# Sheet1.net
KiCad netlist of a schematic drawn in Altium Designer
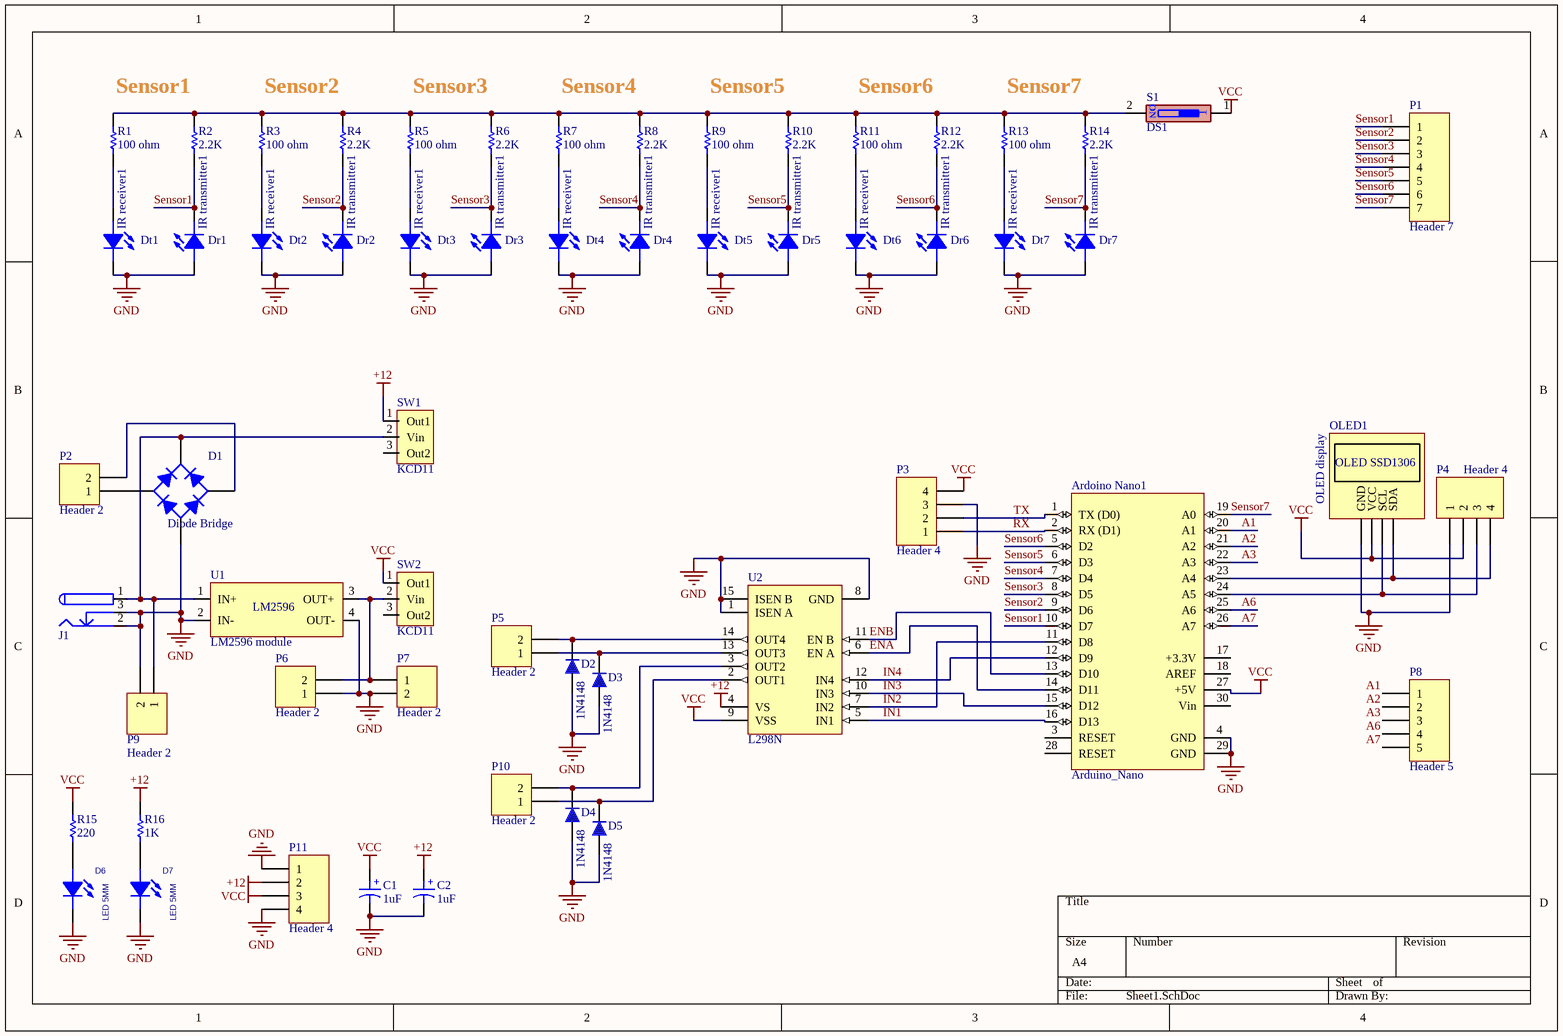
[diagram p0: Sheet1.SchDoc]

(export (version "E")
  (design (tool "Eeschema 10.0.6"))
  (components
    (comp (ref "Ardoino Nano1")
      (value "Arduino_Nano")
      (footprint "Arduino_Nano")
      (libsource (lib "MyLibrary") (part "Arduino_Nano"))
    )
    (comp (ref "C1")
      (value "1uF")
      (footprint "Cap electrolitic radial 10x16-5")
      (description "Cap electrolitic radial")
      (fields (field (name "DESIGNER") "Abbas Basereh"))
      (libsource (lib "Altium") (part "Cap ELECTROLITIC TOTAL SIZE"))
    )
    (comp (ref "C2")
      (value "1uF")
      (footprint "Cap electrolitic radial 10x16-5")
      (description "Cap electrolitic radial")
      (fields (field (name "DESIGNER") "Abbas Basereh"))
      (libsource (lib "Altium") (part "Cap ELECTROLITIC TOTAL SIZE"))
    )
    (comp (ref "D1")
      (value "Diode Bridge")
      (footprint "Bridge KBP PACKAGE")
      (description "Full Wave Diode Bridge")
      (fields (field (name "DESIGNER") "Abbas Basereh"))
      (libsource (lib "Altium") (part "Diode Bridge TOTAL SIZE"))
    )
    (comp (ref "D2")
      (value "1N4148")
      (footprint "DO 35")
      (description "DIODE GEN PURP 100V 200MA DO35")
      (fields (field (name "PUBLISHER") "Abbas Basereh"))
      (libsource (lib "Altium") (part "1N4148"))
    )
    (comp (ref "D3")
      (value "1N4148")
      (footprint "DO 35")
      (description "DIODE GEN PURP 100V 200MA DO35")
      (fields (field (name "PUBLISHER") "Abbas Basereh"))
      (libsource (lib "Altium") (part "1N4148"))
    )
    (comp (ref "D4")
      (value "1N4148")
      (footprint "DO 35")
      (description "DIODE GEN PURP 100V 200MA DO35")
      (fields (field (name "PUBLISHER") "Abbas Basereh"))
      (libsource (lib "Altium") (part "1N4148"))
    )
    (comp (ref "D5")
      (value "1N4148")
      (footprint "DO 35")
      (description "DIODE GEN PURP 100V 200MA DO35")
      (fields (field (name "PUBLISHER") "Abbas Basereh"))
      (libsource (lib "Altium") (part "1N4148"))
    )
    (comp (ref "D6")
      (value "LED 5MM")
      (footprint "LED5MM_RED")
      (description "Light Emitting Diode")
      (fields (field (name "DESIGNER") "Abbas Basereh"))
      (libsource (lib "Altium") (part "LED 5MM"))
    )
    (comp (ref "D7")
      (value "LED 5MM")
      (footprint "LED5MM_RED")
      (description "Light Emitting Diode")
      (fields (field (name "DESIGNER") "Abbas Basereh"))
      (libsource (lib "Altium") (part "LED 5MM"))
    )
    (comp (ref "Dr1")
      (value "IR transmitter1")
      (footprint "LED3mm_GRN")
      (description "Light Emitting Diode")
      (fields (field (name "DESIGNER") "Ali Hafizi"))
      (libsource (lib "Altium") (part "LED 3MM"))
    )
    (comp (ref "Dr2")
      (value "IR transmitter1")
      (footprint "LED3mm_GRN")
      (description "Light Emitting Diode")
      (fields (field (name "DESIGNER") "Ali Hafizi"))
      (libsource (lib "Altium") (part "LED 3MM"))
    )
    (comp (ref "Dr3")
      (value "IR transmitter1")
      (footprint "LED3mm_GRN")
      (description "Light Emitting Diode")
      (fields (field (name "DESIGNER") "Ali Hafizi"))
      (libsource (lib "Altium") (part "LED 3MM"))
    )
    (comp (ref "Dr4")
      (value "IR transmitter1")
      (footprint "LED3mm_GRN")
      (description "Light Emitting Diode")
      (fields (field (name "DESIGNER") "Ali Hafizi"))
      (libsource (lib "Altium") (part "LED 3MM"))
    )
    (comp (ref "Dr5")
      (value "IR transmitter1")
      (footprint "LED3mm_GRN")
      (description "Light Emitting Diode")
      (fields (field (name "DESIGNER") "Ali Hafizi"))
      (libsource (lib "Altium") (part "LED 3MM"))
    )
    (comp (ref "Dr6")
      (value "IR transmitter1")
      (footprint "LED3mm_GRN")
      (description "Light Emitting Diode")
      (fields (field (name "DESIGNER") "Ali Hafizi"))
      (libsource (lib "Altium") (part "LED 3MM"))
    )
    (comp (ref "Dr7")
      (value "IR transmitter1")
      (footprint "LED3mm_GRN")
      (description "Light Emitting Diode")
      (fields (field (name "DESIGNER") "Ali Hafizi"))
      (libsource (lib "Altium") (part "LED 3MM"))
    )
    (comp (ref "Dt1")
      (value "IR receiver1")
      (footprint "LED3mm_GRN")
      (description "Light Emitting Diode")
      (fields (field (name "DESIGNER") "Ali Hafizi"))
      (libsource (lib "Altium") (part "LED 3MM"))
    )
    (comp (ref "Dt2")
      (value "IR receiver1")
      (footprint "LED3mm_GRN")
      (description "Light Emitting Diode")
      (fields (field (name "DESIGNER") "Ali Hafizi"))
      (libsource (lib "Altium") (part "LED 3MM"))
    )
    (comp (ref "Dt3")
      (value "IR receiver1")
      (footprint "LED3mm_GRN")
      (description "Light Emitting Diode")
      (fields (field (name "DESIGNER") "Ali Hafizi"))
      (libsource (lib "Altium") (part "LED 3MM"))
    )
    (comp (ref "Dt4")
      (value "IR receiver1")
      (footprint "LED3mm_GRN")
      (description "Light Emitting Diode")
      (fields (field (name "DESIGNER") "Ali Hafizi"))
      (libsource (lib "Altium") (part "LED 3MM"))
    )
    (comp (ref "Dt5")
      (value "IR receiver1")
      (footprint "LED3mm_GRN")
      (description "Light Emitting Diode")
      (fields (field (name "DESIGNER") "Ali Hafizi"))
      (libsource (lib "Altium") (part "LED 3MM"))
    )
    (comp (ref "Dt6")
      (value "IR receiver1")
      (footprint "LED3mm_GRN")
      (description "Light Emitting Diode")
      (fields (field (name "DESIGNER") "Ali Hafizi"))
      (libsource (lib "Altium") (part "LED 3MM"))
    )
    (comp (ref "Dt7")
      (value "IR receiver1")
      (footprint "LED3mm_GRN")
      (description "Light Emitting Diode")
      (fields (field (name "DESIGNER") "Ali Hafizi"))
      (libsource (lib "Altium") (part "LED 3MM"))
    )
    (comp (ref "J1")
      (value "DC Power Jack")
      (footprint "DC Power Jack 1")
      (description "DC Power Jack. Center Pin 2.5mm. Diameter: 5.7mm")
      (fields (field (name "DESIGNER") "Ali Hafizi"))
      (libsource (lib "Altium") (part "DC Power Jack"))
    )
    (comp (ref "OLED1")
      (value "OLED display")
      (footprint "OLED-SSD1306")
      (description "OLED display SSD1306 0.96 inch 64*128px")
      (libsource (lib "MyLibrary") (part "OLED-SSD1306"))
    )
    (comp (ref "P1")
      (value "Header 7")
      (footprint "HDR1X7")
      (description "Header, 7-Pin")
      (fields (field (name "PUBLISHER") "Altium Limited"))
      (libsource (lib "Altium") (part "Header 7"))
    )
    (comp (ref "P2")
      (value "Header 2")
      (footprint "HDR1X2")
      (description "Header, 2-Pin")
      (fields (field (name "PUBLISHER") "Altium Limited"))
      (libsource (lib "Altium") (part "Header 2"))
    )
    (comp (ref "P3")
      (value "Header 4")
      (footprint "HDR1X4")
      (description "Header, 4-Pin")
      (fields (field (name "PUBLISHER") "Altium Limited"))
      (libsource (lib "") (part "Header 4_2"))
    )
    (comp (ref "P4")
      (value "Header 4")
      (footprint "HDR1X4")
      (description "Header, 4-Pin")
      (fields (field (name "PUBLISHER") "Altium Limited"))
      (libsource (lib "Altium") (part "Header 4"))
    )
    (comp (ref "P5")
      (value "Header 2")
      (footprint "HDR1X2")
      (description "Header, 2-Pin")
      (fields (field (name "PUBLISHER") "Altium Limited"))
      (libsource (lib "Altium") (part "Header 2"))
    )
    (comp (ref "P6")
      (value "Header 2")
      (footprint "HDR1X2")
      (description "Header, 2-Pin")
      (fields (field (name "PUBLISHER") "Altium Limited"))
      (libsource (lib "Altium") (part "Header 2"))
    )
    (comp (ref "P7")
      (value "Header 2")
      (footprint "HDR1X2")
      (description "Header, 2-Pin")
      (fields (field (name "PUBLISHER") "Altium Limited"))
      (libsource (lib "") (part "Header 2_1"))
    )
    (comp (ref "P8")
      (value "Header 5")
      (footprint "HDR1X5")
      (description "Header, 5-Pin")
      (fields (field (name "PUBLISHER") "Altium Limited"))
      (libsource (lib "Altium") (part "Header 5"))
    )
    (comp (ref "P9")
      (value "Header 2")
      (footprint "HDR1X2")
      (description "Header, 2-Pin")
      (fields (field (name "PUBLISHER") "Altium Limited"))
      (libsource (lib "") (part "Header 2_2"))
    )
    (comp (ref "P10")
      (value "Header 2")
      (footprint "HDR1X2")
      (description "Header, 2-Pin")
      (fields (field (name "PUBLISHER") "Altium Limited"))
      (libsource (lib "Altium") (part "Header 2"))
    )
    (comp (ref "P11")
      (value "Header 4")
      (footprint "HDR1X4")
      (description "Header, 4-Pin")
      (fields (field (name "PUBLISHER") "Altium Limited"))
      (libsource (lib "") (part "Header 4_1"))
    )
    (comp (ref "R1")
      (value "100 ohm")
      (footprint "Axial 0_25 W, 0_4 IN LEAD PITCH")
      (description "RES Axial 0.25W")
      (fields (field (name "DESIGNER") "Abbas Basereh"))
      (libsource (lib "Altium") (part "RES Axial 0.25W"))
    )
    (comp (ref "R2")
      (value "2.2K")
      (footprint "Axial 0_25 W, 0_4 IN LEAD PITCH")
      (description "RES Axial 0.25W")
      (fields (field (name "DESIGNER") "Abbas Basereh"))
      (libsource (lib "Altium") (part "RES Axial 0.25W"))
    )
    (comp (ref "R3")
      (value "100 ohm")
      (footprint "Axial 0_25 W, 0_4 IN LEAD PITCH")
      (description "RES Axial 0.25W")
      (fields (field (name "DESIGNER") "Abbas Basereh"))
      (libsource (lib "Altium") (part "RES Axial 0.25W"))
    )
    (comp (ref "R4")
      (value "2.2K")
      (footprint "Axial 0_25 W, 0_4 IN LEAD PITCH")
      (description "RES Axial 0.25W")
      (fields (field (name "DESIGNER") "Abbas Basereh"))
      (libsource (lib "Altium") (part "RES Axial 0.25W"))
    )
    (comp (ref "R5")
      (value "100 ohm")
      (footprint "Axial 0_25 W, 0_4 IN LEAD PITCH")
      (description "RES Axial 0.25W")
      (fields (field (name "DESIGNER") "Abbas Basereh"))
      (libsource (lib "Altium") (part "RES Axial 0.25W"))
    )
    (comp (ref "R6")
      (value "2.2K")
      (footprint "Axial 0_25 W, 0_4 IN LEAD PITCH")
      (description "RES Axial 0.25W")
      (fields (field (name "DESIGNER") "Abbas Basereh"))
      (libsource (lib "Altium") (part "RES Axial 0.25W"))
    )
    (comp (ref "R7")
      (value "100 ohm")
      (footprint "Axial 0_25 W, 0_4 IN LEAD PITCH")
      (description "RES Axial 0.25W")
      (fields (field (name "DESIGNER") "Abbas Basereh"))
      (libsource (lib "Altium") (part "RES Axial 0.25W"))
    )
    (comp (ref "R8")
      (value "2.2K")
      (footprint "Axial 0_25 W, 0_4 IN LEAD PITCH")
      (description "RES Axial 0.25W")
      (fields (field (name "DESIGNER") "Abbas Basereh"))
      (libsource (lib "Altium") (part "RES Axial 0.25W"))
    )
    (comp (ref "R9")
      (value "100 ohm")
      (footprint "Axial 0_25 W, 0_4 IN LEAD PITCH")
      (description "RES Axial 0.25W")
      (fields (field (name "DESIGNER") "Abbas Basereh"))
      (libsource (lib "Altium") (part "RES Axial 0.25W"))
    )
    (comp (ref "R10")
      (value "2.2K")
      (footprint "Axial 0_25 W, 0_4 IN LEAD PITCH")
      (description "RES Axial 0.25W")
      (fields (field (name "DESIGNER") "Abbas Basereh"))
      (libsource (lib "Altium") (part "RES Axial 0.25W"))
    )
    (comp (ref "R11")
      (value "100 ohm")
      (footprint "Axial 0_25 W, 0_4 IN LEAD PITCH")
      (description "RES Axial 0.25W")
      (fields (field (name "DESIGNER") "Abbas Basereh"))
      (libsource (lib "Altium") (part "RES Axial 0.25W"))
    )
    (comp (ref "R12")
      (value "2.2K")
      (footprint "Axial 0_25 W, 0_4 IN LEAD PITCH")
      (description "RES Axial 0.25W")
      (fields (field (name "DESIGNER") "Abbas Basereh"))
      (libsource (lib "Altium") (part "RES Axial 0.25W"))
    )
    (comp (ref "R13")
      (value "100 ohm")
      (footprint "Axial 0_25 W, 0_4 IN LEAD PITCH")
      (description "RES Axial 0.25W")
      (fields (field (name "DESIGNER") "Abbas Basereh"))
      (libsource (lib "Altium") (part "RES Axial 0.25W"))
    )
    (comp (ref "R14")
      (value "2.2K")
      (footprint "Axial 0_25 W, 0_4 IN LEAD PITCH")
      (description "RES Axial 0.25W")
      (fields (field (name "DESIGNER") "Abbas Basereh"))
      (libsource (lib "Altium") (part "RES Axial 0.25W"))
    )
    (comp (ref "R15")
      (value "220")
      (footprint "Axial 0_25 W, 0_4 IN LEAD PITCH")
      (description "RES Axial 0.25W")
      (fields (field (name "DESIGNER") "Abbas Basereh"))
      (libsource (lib "Altium") (part "RES Axial 0.25W"))
    )
    (comp (ref "R16")
      (value "1K")
      (footprint "Axial 0_25 W, 0_4 IN LEAD PITCH")
      (description "RES Axial 0.25W")
      (fields (field (name "DESIGNER") "Abbas Basereh"))
      (libsource (lib "Altium") (part "RES Axial 0.25W"))
    )
    (comp (ref "S1")
      (value "DS1")
      (footprint "DIP Switch x1")
      (description "1 BIT DIP Switch")
      (libsource (lib "Altium") (part "DIP Switch 1"))
    )
    (comp (ref "SW1")
      (value "KCD11")
      (footprint "KCD11 rocker switch")
      (description "KCD11 rocker switch 2 state off/on")
      (libsource (lib "MyLibrary") (part "KCD11"))
    )
    (comp (ref "SW2")
      (value "KCD11")
      (footprint "KCD11 rocker switch")
      (description "KCD11 rocker switch 2 state off/on")
      (libsource (lib "MyLibrary") (part "KCD11"))
    )
    (comp (ref "U1")
      (value "LM2596 module")
      (footprint "LM2596 module")
      (description "LM2596 DC-DC module 1.25V-30V 3A")
      (libsource (lib "MyLibrary") (part "LM2596 module"))
    )
    (comp (ref "U2")
      (value "L298N")
      (footprint "Multiwatt15V")
      (description "Dual Full Bridge Driver")
      (fields (field (name "PUBLISHER") "Altium Limited"))
      (libsource (lib "Altium") (part "L298N"))
    )
  )
  (nets
    (net (code "1") (name "+12") (class "Default")
      (node (ref "C2") (pin "1") (pinfunction "1_1") (pintype "passive"))
      (node (ref "P11") (pin "2") (pinfunction "2_2") (pintype "passive"))
      (node (ref "R16") (pin "2") (pinfunction "2_2") (pintype "passive"))
      (node (ref "SW1") (pin "1") (pinfunction "Out1_1") (pintype "passive"))
      (node (ref "U2") (pin "4") (pinfunction "VS_4") (pintype "power_in"))
    )
    (net (code "2") (name "/A1") (class "Default")
      (node (ref "Ardoino Nano1") (pin "20") (pinfunction "A1_20") (pintype "bidirectional"))
      (node (ref "P8") (pin "1") (pinfunction "1_1") (pintype "passive"))
    )
    (net (code "3") (name "/A2") (class "Default")
      (node (ref "Ardoino Nano1") (pin "21") (pinfunction "A2_21") (pintype "bidirectional"))
      (node (ref "P8") (pin "2") (pinfunction "2_2") (pintype "passive"))
    )
    (net (code "4") (name "/A3") (class "Default")
      (node (ref "Ardoino Nano1") (pin "22") (pinfunction "A3_22") (pintype "bidirectional"))
      (node (ref "P8") (pin "3") (pinfunction "3_3") (pintype "passive"))
    )
    (net (code "5") (name "/A6") (class "Default")
      (node (ref "Ardoino Nano1") (pin "25") (pinfunction "A6_25") (pintype "bidirectional"))
      (node (ref "P8") (pin "4") (pinfunction "4_4") (pintype "passive"))
    )
    (net (code "6") (name "/A7") (class "Default")
      (node (ref "Ardoino Nano1") (pin "26") (pinfunction "A7_26") (pintype "bidirectional"))
      (node (ref "P8") (pin "5") (pinfunction "5_5") (pintype "passive"))
    )
    (net (code "7") (name "/ENA") (class "Default")
      (node (ref "Ardoino Nano1") (pin "14") (pinfunction "D11_14") (pintype "bidirectional"))
      (node (ref "U2") (pin "6") (pinfunction "EN_A_6") (pintype "input"))
    )
    (net (code "8") (name "/ENB") (class "Default")
      (node (ref "Ardoino Nano1") (pin "13") (pinfunction "D10_13") (pintype "bidirectional"))
      (node (ref "U2") (pin "11") (pinfunction "EN_B_11") (pintype "input"))
    )
    (net (code "9") (name "/IN1") (class "Default")
      (node (ref "Ardoino Nano1") (pin "16") (pinfunction "D13_16") (pintype "bidirectional"))
      (node (ref "U2") (pin "5") (pinfunction "IN1_5") (pintype "input"))
    )
    (net (code "10") (name "/IN2") (class "Default")
      (node (ref "Ardoino Nano1") (pin "11") (pinfunction "D8_11") (pintype "bidirectional"))
      (node (ref "U2") (pin "7") (pinfunction "IN2_7") (pintype "input"))
    )
    (net (code "11") (name "/IN3") (class "Default")
      (node (ref "Ardoino Nano1") (pin "15") (pinfunction "D12_15") (pintype "bidirectional"))
      (node (ref "U2") (pin "10") (pinfunction "IN3_10") (pintype "input"))
    )
    (net (code "12") (name "/IN4") (class "Default")
      (node (ref "Ardoino Nano1") (pin "12") (pinfunction "D9_12") (pintype "bidirectional"))
      (node (ref "U2") (pin "12") (pinfunction "IN4_12") (pintype "input"))
    )
    (net (code "13") (name "/RX") (class "Default")
      (node (ref "Ardoino Nano1") (pin "2") (pinfunction "RX_(D1)_2") (pintype "bidirectional"))
      (node (ref "P3") (pin "1") (pinfunction "1_1") (pintype "passive"))
    )
    (net (code "14") (name "/Sensor1") (class "Default")
      (node (ref "Ardoino Nano1") (pin "10") (pinfunction "D7_10") (pintype "bidirectional"))
      (node (ref "Dr1") (pin "2") (pinfunction "CATHODE_2") (pintype "passive"))
      (node (ref "P1") (pin "1") (pinfunction "1_1") (pintype "passive"))
      (node (ref "R2") (pin "1") (pinfunction "1_1") (pintype "passive"))
    )
    (net (code "15") (name "/Sensor2") (class "Default")
      (node (ref "Ardoino Nano1") (pin "9") (pinfunction "D6_9") (pintype "bidirectional"))
      (node (ref "Dr2") (pin "2") (pinfunction "CATHODE_2") (pintype "passive"))
      (node (ref "P1") (pin "2") (pinfunction "2_2") (pintype "passive"))
      (node (ref "R4") (pin "1") (pinfunction "1_1") (pintype "passive"))
    )
    (net (code "16") (name "/Sensor3") (class "Default")
      (node (ref "Ardoino Nano1") (pin "8") (pinfunction "D5_8") (pintype "bidirectional"))
      (node (ref "Dr3") (pin "2") (pinfunction "CATHODE_2") (pintype "passive"))
      (node (ref "P1") (pin "3") (pinfunction "3_3") (pintype "passive"))
      (node (ref "R6") (pin "1") (pinfunction "1_1") (pintype "passive"))
    )
    (net (code "17") (name "/Sensor4") (class "Default")
      (node (ref "Ardoino Nano1") (pin "7") (pinfunction "D4_7") (pintype "bidirectional"))
      (node (ref "Dr4") (pin "2") (pinfunction "CATHODE_2") (pintype "passive"))
      (node (ref "P1") (pin "4") (pinfunction "4_4") (pintype "passive"))
      (node (ref "R8") (pin "1") (pinfunction "1_1") (pintype "passive"))
    )
    (net (code "18") (name "/Sensor5") (class "Default")
      (node (ref "Ardoino Nano1") (pin "6") (pinfunction "D3_6") (pintype "bidirectional"))
      (node (ref "Dr5") (pin "2") (pinfunction "CATHODE_2") (pintype "passive"))
      (node (ref "P1") (pin "5") (pinfunction "5_5") (pintype "passive"))
      (node (ref "R10") (pin "1") (pinfunction "1_1") (pintype "passive"))
    )
    (net (code "19") (name "/Sensor6") (class "Default")
      (node (ref "Ardoino Nano1") (pin "5") (pinfunction "D2_5") (pintype "bidirectional"))
      (node (ref "Dr6") (pin "2") (pinfunction "CATHODE_2") (pintype "passive"))
      (node (ref "P1") (pin "6") (pinfunction "6_6") (pintype "passive"))
      (node (ref "R12") (pin "1") (pinfunction "1_1") (pintype "passive"))
    )
    (net (code "20") (name "/Sensor7") (class "Default")
      (node (ref "Ardoino Nano1") (pin "19") (pinfunction "A0_19") (pintype "bidirectional"))
      (node (ref "Dr7") (pin "2") (pinfunction "CATHODE_2") (pintype "passive"))
      (node (ref "P1") (pin "7") (pinfunction "7_7") (pintype "passive"))
      (node (ref "R14") (pin "1") (pinfunction "1_1") (pintype "passive"))
    )
    (net (code "21") (name "/TX") (class "Default")
      (node (ref "Ardoino Nano1") (pin "1") (pinfunction "TX_(D0)_1") (pintype "bidirectional"))
      (node (ref "P3") (pin "2") (pinfunction "2_2") (pintype "passive"))
    )
    (net (code "22") (name "GND") (class "Default")
      (node (ref "Ardoino Nano1") (pin "29") (pinfunction "GND_29") (pintype "passive"))
      (node (ref "Ardoino Nano1") (pin "4") (pinfunction "GND_4") (pintype "passive"))
      (node (ref "C1") (pin "2") (pinfunction "2_2") (pintype "passive"))
      (node (ref "C2") (pin "2") (pinfunction "2_2") (pintype "passive"))
      (node (ref "D1") (pin "4") (pinfunction "-_4") (pintype "passive"))
      (node (ref "D2") (pin "1") (pintype "passive"))
      (node (ref "D3") (pin "1") (pintype "passive"))
      (node (ref "D4") (pin "1") (pintype "passive"))
      (node (ref "D5") (pin "1") (pintype "passive"))
      (node (ref "D6") (pin "2") (pinfunction "CATHODE_2") (pintype "passive"))
      (node (ref "D7") (pin "2") (pinfunction "CATHODE_2") (pintype "passive"))
      (node (ref "Dr1") (pin "1") (pinfunction "ANODE_1") (pintype "passive"))
      (node (ref "Dr2") (pin "1") (pinfunction "ANODE_1") (pintype "passive"))
      (node (ref "Dr3") (pin "1") (pinfunction "ANODE_1") (pintype "passive"))
      (node (ref "Dr4") (pin "1") (pinfunction "ANODE_1") (pintype "passive"))
      (node (ref "Dr5") (pin "1") (pinfunction "ANODE_1") (pintype "passive"))
      (node (ref "Dr6") (pin "1") (pinfunction "ANODE_1") (pintype "passive"))
      (node (ref "Dr7") (pin "1") (pinfunction "ANODE_1") (pintype "passive"))
      (node (ref "Dt1") (pin "2") (pinfunction "CATHODE_2") (pintype "passive"))
      (node (ref "Dt2") (pin "2") (pinfunction "CATHODE_2") (pintype "passive"))
      (node (ref "Dt3") (pin "2") (pinfunction "CATHODE_2") (pintype "passive"))
      (node (ref "Dt4") (pin "2") (pinfunction "CATHODE_2") (pintype "passive"))
      (node (ref "Dt5") (pin "2") (pinfunction "CATHODE_2") (pintype "passive"))
      (node (ref "Dt6") (pin "2") (pinfunction "CATHODE_2") (pintype "passive"))
      (node (ref "Dt7") (pin "2") (pinfunction "CATHODE_2") (pintype "passive"))
      (node (ref "J1") (pin "2") (pinfunction "2_2") (pintype "power_in"))
      (node (ref "J1") (pin "3") (pinfunction "3_3") (pintype "power_in"))
      (node (ref "OLED1") (pin "GND") (pinfunction "GND_GND") (pintype "passive"))
      (node (ref "P11") (pin "1") (pinfunction "1_1") (pintype "passive"))
      (node (ref "P11") (pin "4") (pinfunction "4_4") (pintype "passive"))
      (node (ref "P3") (pin "3") (pinfunction "3_3") (pintype "passive"))
      (node (ref "P4") (pin "1") (pinfunction "1_1") (pintype "passive"))
      (node (ref "P6") (pin "1") (pinfunction "1_1") (pintype "passive"))
      (node (ref "P7") (pin "2") (pinfunction "2_2") (pintype "passive"))
      (node (ref "P9") (pin "2") (pinfunction "2_2") (pintype "passive"))
      (node (ref "U1") (pin "2") (pinfunction "IN-_2") (pintype "passive"))
      (node (ref "U1") (pin "4") (pinfunction "OUT-_4") (pintype "passive"))
      (node (ref "U2") (pin "1") (pinfunction "ISEN_A_1") (pintype "passive"))
      (node (ref "U2") (pin "15") (pinfunction "ISEN_B_15") (pintype "passive"))
      (node (ref "U2") (pin "8") (pinfunction "GND_8") (pintype "power_in"))
    )
    (net (code "23") (name "Net-(Ardoino Nano1-A4)") (class "Default")
      (node (ref "Ardoino Nano1") (pin "23") (pinfunction "A4_23") (pintype "bidirectional"))
      (node (ref "OLED1") (pin "SDA") (pinfunction "SDA_SDA") (pintype "passive"))
      (node (ref "P4") (pin "4") (pinfunction "4_4") (pintype "passive"))
    )
    (net (code "24") (name "Net-(Ardoino Nano1-A5)") (class "Default")
      (node (ref "Ardoino Nano1") (pin "24") (pinfunction "A5_24") (pintype "bidirectional"))
      (node (ref "OLED1") (pin "SCL") (pinfunction "SCL_SCL") (pintype "passive"))
      (node (ref "P4") (pin "3") (pinfunction "3_3") (pintype "passive"))
    )
    (net (code "25") (name "Net-(D1-+)") (class "Default")
      (node (ref "D1") (pin "1") (pinfunction "+_1") (pintype "passive"))
      (node (ref "J1") (pin "1") (pinfunction "1_1") (pintype "power_in"))
      (node (ref "P9") (pin "1") (pinfunction "1_1") (pintype "passive"))
      (node (ref "SW1") (pin "2") (pinfunction "Vin_2") (pintype "passive"))
      (node (ref "U1") (pin "1") (pinfunction "IN+_1") (pintype "passive"))
    )
    (net (code "26") (name "Net-(D1-AC-Pad2)") (class "Default")
      (node (ref "D1") (pin "2") (pinfunction "AC_2") (pintype "passive"))
      (node (ref "P2") (pin "1") (pinfunction "1_1") (pintype "passive"))
    )
    (net (code "27") (name "Net-(D1-AC-Pad3)") (class "Default")
      (node (ref "D1") (pin "3") (pinfunction "AC_3") (pintype "passive"))
      (node (ref "P2") (pin "2") (pinfunction "2_2") (pintype "passive"))
    )
    (net (code "28") (name "Net-(D6-ANODE)") (class "Default")
      (node (ref "D6") (pin "1") (pinfunction "ANODE_1") (pintype "passive"))
      (node (ref "R15") (pin "1") (pinfunction "1_1") (pintype "passive"))
    )
    (net (code "29") (name "Net-(D7-ANODE)") (class "Default")
      (node (ref "D7") (pin "1") (pinfunction "ANODE_1") (pintype "passive"))
      (node (ref "R16") (pin "1") (pinfunction "1_1") (pintype "passive"))
    )
    (net (code "30") (name "Net-(Dt1-ANODE)") (class "Default")
      (node (ref "Dt1") (pin "1") (pinfunction "ANODE_1") (pintype "passive"))
      (node (ref "R1") (pin "1") (pinfunction "1_1") (pintype "passive"))
    )
    (net (code "31") (name "Net-(Dt2-ANODE)") (class "Default")
      (node (ref "Dt2") (pin "1") (pinfunction "ANODE_1") (pintype "passive"))
      (node (ref "R3") (pin "1") (pinfunction "1_1") (pintype "passive"))
    )
    (net (code "32") (name "Net-(Dt3-ANODE)") (class "Default")
      (node (ref "Dt3") (pin "1") (pinfunction "ANODE_1") (pintype "passive"))
      (node (ref "R5") (pin "1") (pinfunction "1_1") (pintype "passive"))
    )
    (net (code "33") (name "Net-(Dt4-ANODE)") (class "Default")
      (node (ref "Dt4") (pin "1") (pinfunction "ANODE_1") (pintype "passive"))
      (node (ref "R7") (pin "1") (pinfunction "1_1") (pintype "passive"))
    )
    (net (code "34") (name "Net-(Dt5-ANODE)") (class "Default")
      (node (ref "Dt5") (pin "1") (pinfunction "ANODE_1") (pintype "passive"))
      (node (ref "R9") (pin "1") (pinfunction "1_1") (pintype "passive"))
    )
    (net (code "35") (name "Net-(Dt6-ANODE)") (class "Default")
      (node (ref "Dt6") (pin "1") (pinfunction "ANODE_1") (pintype "passive"))
      (node (ref "R11") (pin "1") (pinfunction "1_1") (pintype "passive"))
    )
    (net (code "36") (name "Net-(Dt7-ANODE)") (class "Default")
      (node (ref "Dt7") (pin "1") (pinfunction "ANODE_1") (pintype "passive"))
      (node (ref "R13") (pin "1") (pinfunction "1_1") (pintype "passive"))
    )
    (net (code "37") (name "Net-(R1-Pad2)") (class "Default")
      (node (ref "R1") (pin "2") (pinfunction "2_2") (pintype "passive"))
      (node (ref "R10") (pin "2") (pinfunction "2_2") (pintype "passive"))
      (node (ref "R11") (pin "2") (pinfunction "2_2") (pintype "passive"))
      (node (ref "R12") (pin "2") (pinfunction "2_2") (pintype "passive"))
      (node (ref "R13") (pin "2") (pinfunction "2_2") (pintype "passive"))
      (node (ref "R14") (pin "2") (pinfunction "2_2") (pintype "passive"))
      (node (ref "R2") (pin "2") (pinfunction "2_2") (pintype "passive"))
      (node (ref "R3") (pin "2") (pinfunction "2_2") (pintype "passive"))
      (node (ref "R4") (pin "2") (pinfunction "2_2") (pintype "passive"))
      (node (ref "R5") (pin "2") (pinfunction "2_2") (pintype "passive"))
      (node (ref "R6") (pin "2") (pinfunction "2_2") (pintype "passive"))
      (node (ref "R7") (pin "2") (pinfunction "2_2") (pintype "passive"))
      (node (ref "R8") (pin "2") (pinfunction "2_2") (pintype "passive"))
      (node (ref "R9") (pin "2") (pinfunction "2_2") (pintype "passive"))
      (node (ref "S1") (pin "2") (pinfunction "2_2") (pintype "passive"))
    )
    (net (code "38") (name "Net-(SW2-Vin)") (class "Default")
      (node (ref "P6") (pin "2") (pinfunction "2_2") (pintype "passive"))
      (node (ref "P7") (pin "1") (pinfunction "1_1") (pintype "passive"))
      (node (ref "SW2") (pin "2") (pinfunction "Vin_2") (pintype "passive"))
      (node (ref "U1") (pin "3") (pinfunction "OUT+_3") (pintype "passive"))
    )
    (net (code "39") (name "Net-(U2-OUT1)") (class "Default")
      (node (ref "D5") (pin "2") (pintype "passive"))
      (node (ref "P10") (pin "1") (pinfunction "1_1") (pintype "passive"))
      (node (ref "U2") (pin "2") (pinfunction "OUT1_2") (pintype "output"))
    )
    (net (code "40") (name "Net-(U2-OUT2)") (class "Default")
      (node (ref "D4") (pin "2") (pintype "passive"))
      (node (ref "P10") (pin "2") (pinfunction "2_2") (pintype "passive"))
      (node (ref "U2") (pin "3") (pinfunction "OUT2_3") (pintype "output"))
    )
    (net (code "41") (name "Net-(U2-OUT3)") (class "Default")
      (node (ref "D3") (pin "2") (pintype "passive"))
      (node (ref "P5") (pin "1") (pinfunction "1_1") (pintype "passive"))
      (node (ref "U2") (pin "13") (pinfunction "OUT3_13") (pintype "output"))
    )
    (net (code "42") (name "Net-(U2-OUT4)") (class "Default")
      (node (ref "D2") (pin "2") (pintype "passive"))
      (node (ref "P5") (pin "2") (pinfunction "2_2") (pintype "passive"))
      (node (ref "U2") (pin "14") (pinfunction "OUT4_14") (pintype "output"))
    )
    (net (code "43") (name "VCC") (class "Default")
      (node (ref "Ardoino Nano1") (pin "27") (pinfunction "+5V_27") (pintype "passive"))
      (node (ref "C1") (pin "1") (pinfunction "1_1") (pintype "passive"))
      (node (ref "OLED1") (pin "VCC") (pinfunction "VCC_VCC") (pintype "passive"))
      (node (ref "P11") (pin "3") (pinfunction "3_3") (pintype "passive"))
      (node (ref "P3") (pin "4") (pinfunction "4_4") (pintype "passive"))
      (node (ref "P4") (pin "2") (pinfunction "2_2") (pintype "passive"))
      (node (ref "R15") (pin "2") (pinfunction "2_2") (pintype "passive"))
      (node (ref "S1") (pin "1") (pinfunction "1_1") (pintype "passive"))
      (node (ref "SW2") (pin "1") (pinfunction "Out1_1") (pintype "passive"))
      (node (ref "U2") (pin "9") (pinfunction "VSS_9") (pintype "power_in"))
    )
    (net (code "44") (name "unconnected-(Ardoino Nano1-+3.3V-Pad17)") (class "Default")
      (node (ref "Ardoino Nano1") (pin "17") (pinfunction "+3.3V_17") (pintype "passive"))
    )
    (net (code "45") (name "unconnected-(Ardoino Nano1-AREF-Pad18)") (class "Default")
      (node (ref "Ardoino Nano1") (pin "18") (pinfunction "AREF_18") (pintype "passive"))
    )
    (net (code "46") (name "unconnected-(Ardoino Nano1-RESET-Pad3)") (class "Default")
      (node (ref "Ardoino Nano1") (pin "3") (pinfunction "RESET_3") (pintype "passive"))
    )
    (net (code "47") (name "unconnected-(Ardoino Nano1-RESET-Pad28)") (class "Default")
      (node (ref "Ardoino Nano1") (pin "28") (pinfunction "RESET_28") (pintype "passive"))
    )
    (net (code "48") (name "unconnected-(Ardoino Nano1-Vin-Pad30)") (class "Default")
      (node (ref "Ardoino Nano1") (pin "30") (pinfunction "Vin_30") (pintype "passive"))
    )
    (net (code "49") (name "unconnected-(SW1-Out2-Pad3)") (class "Default")
      (node (ref "SW1") (pin "3") (pinfunction "Out2_3") (pintype "passive"))
    )
    (net (code "50") (name "unconnected-(SW2-Out2-Pad3)") (class "Default")
      (node (ref "SW2") (pin "3") (pinfunction "Out2_3") (pintype "passive"))
    )
  )
)
